# NVME.net
KiCad netlist of a schematic drawn in Altium Designer
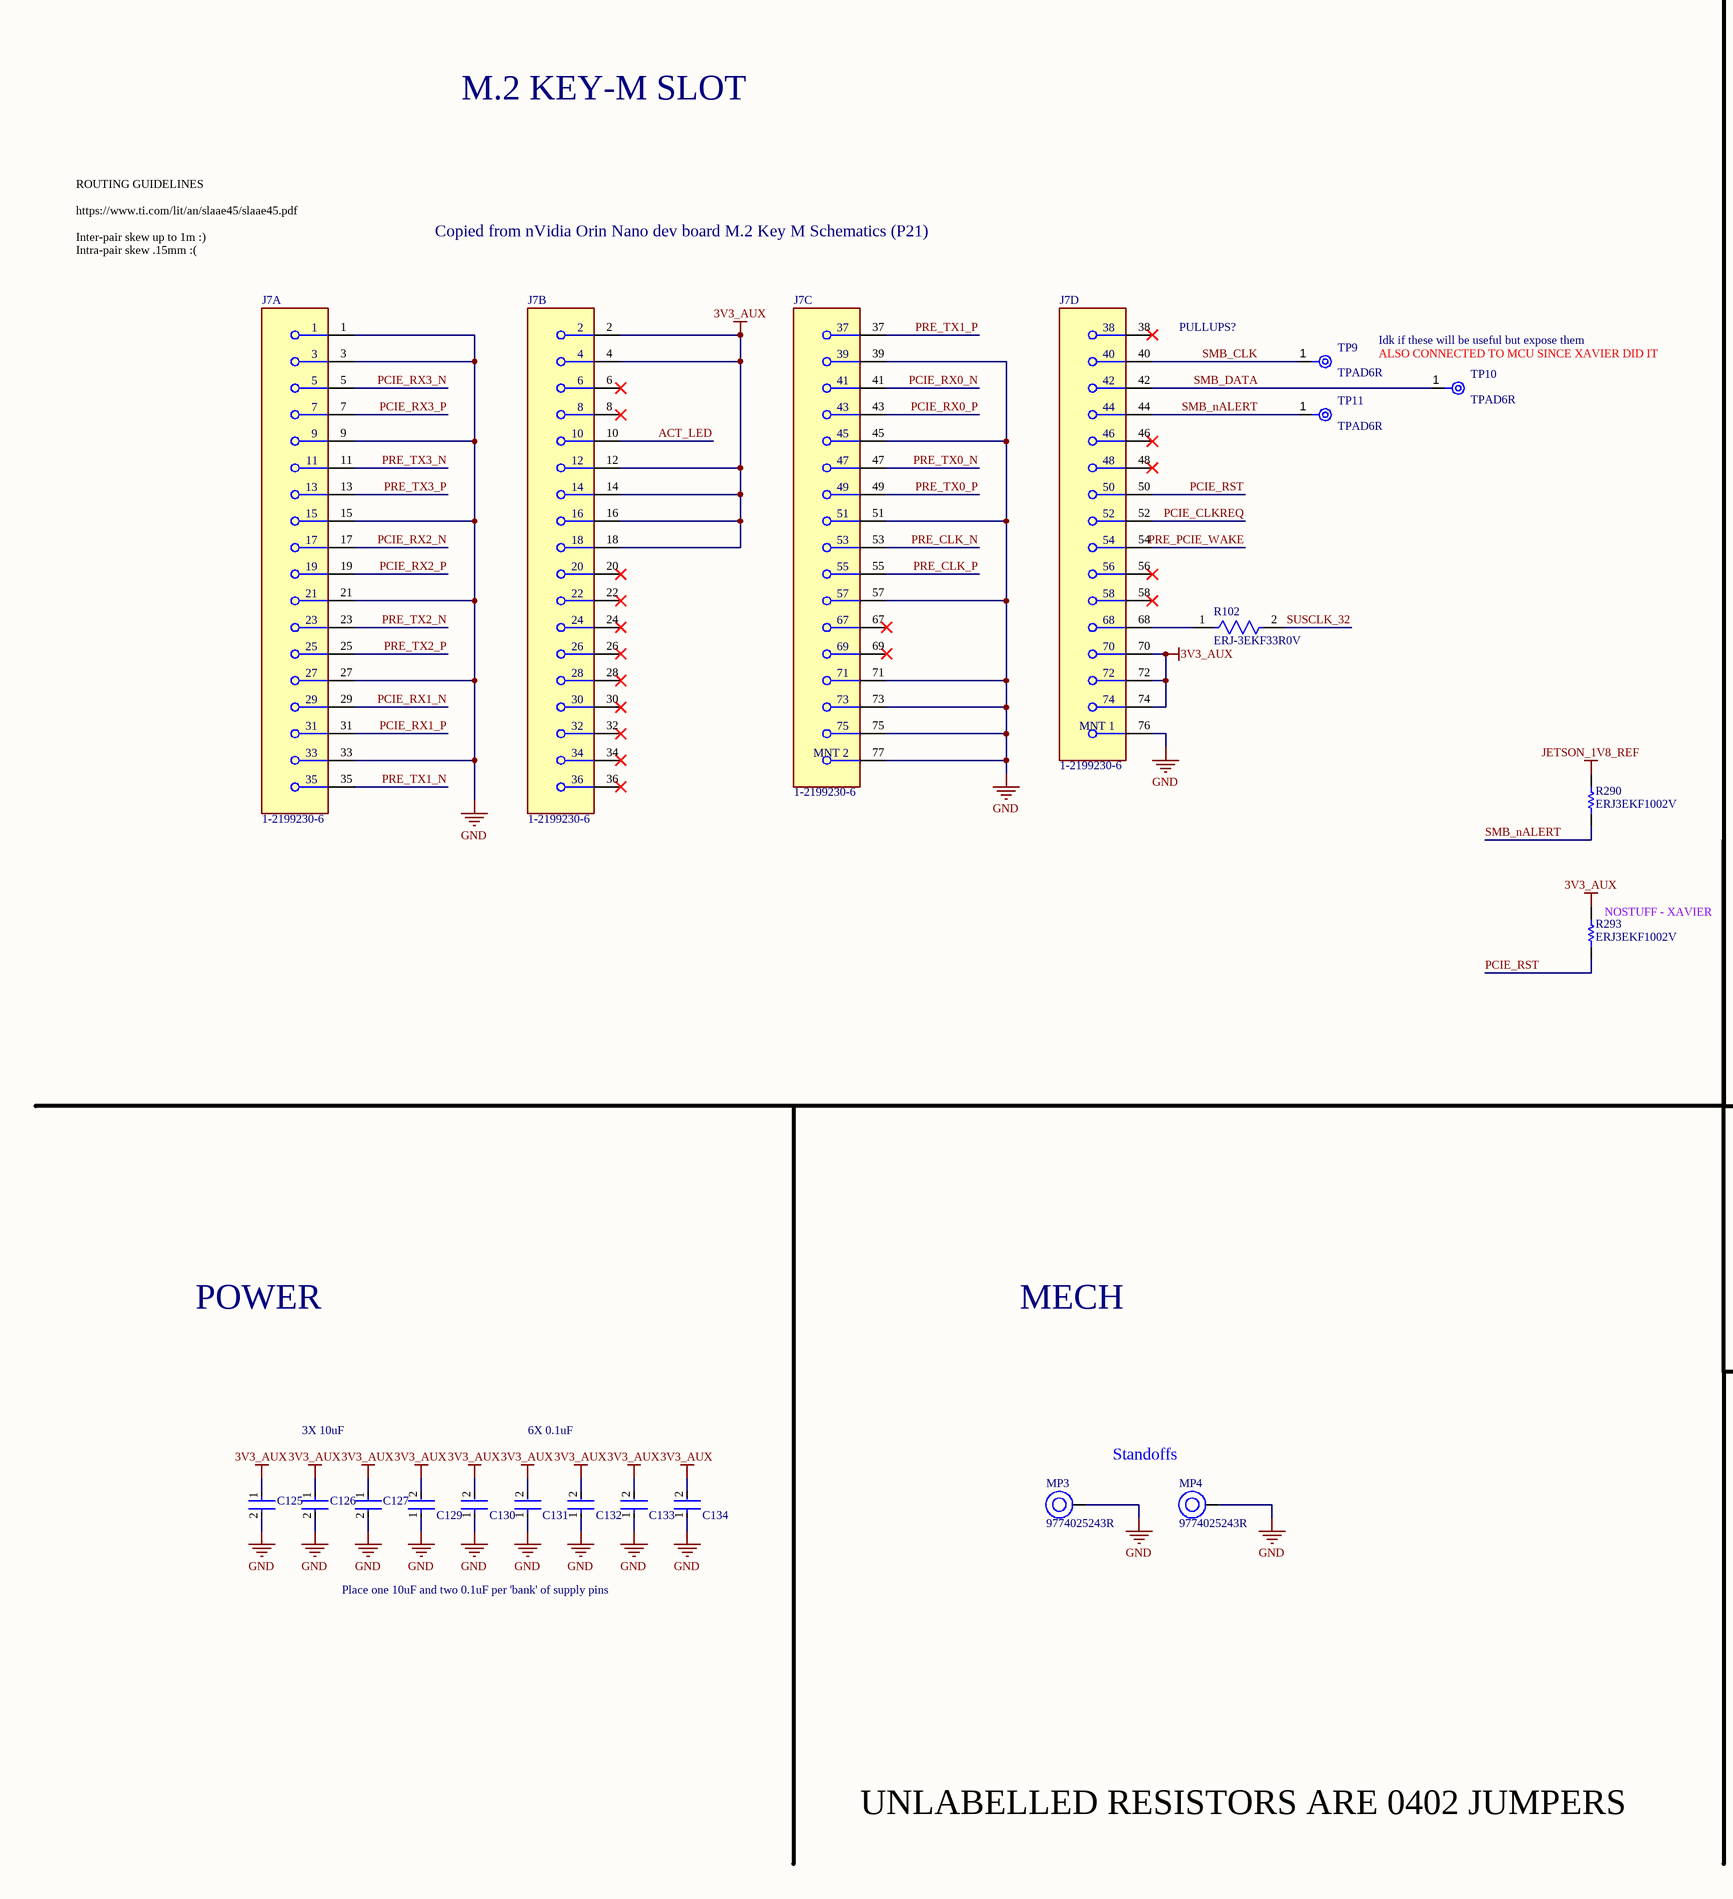
[diagram p0: NVME.SchDoc, left]
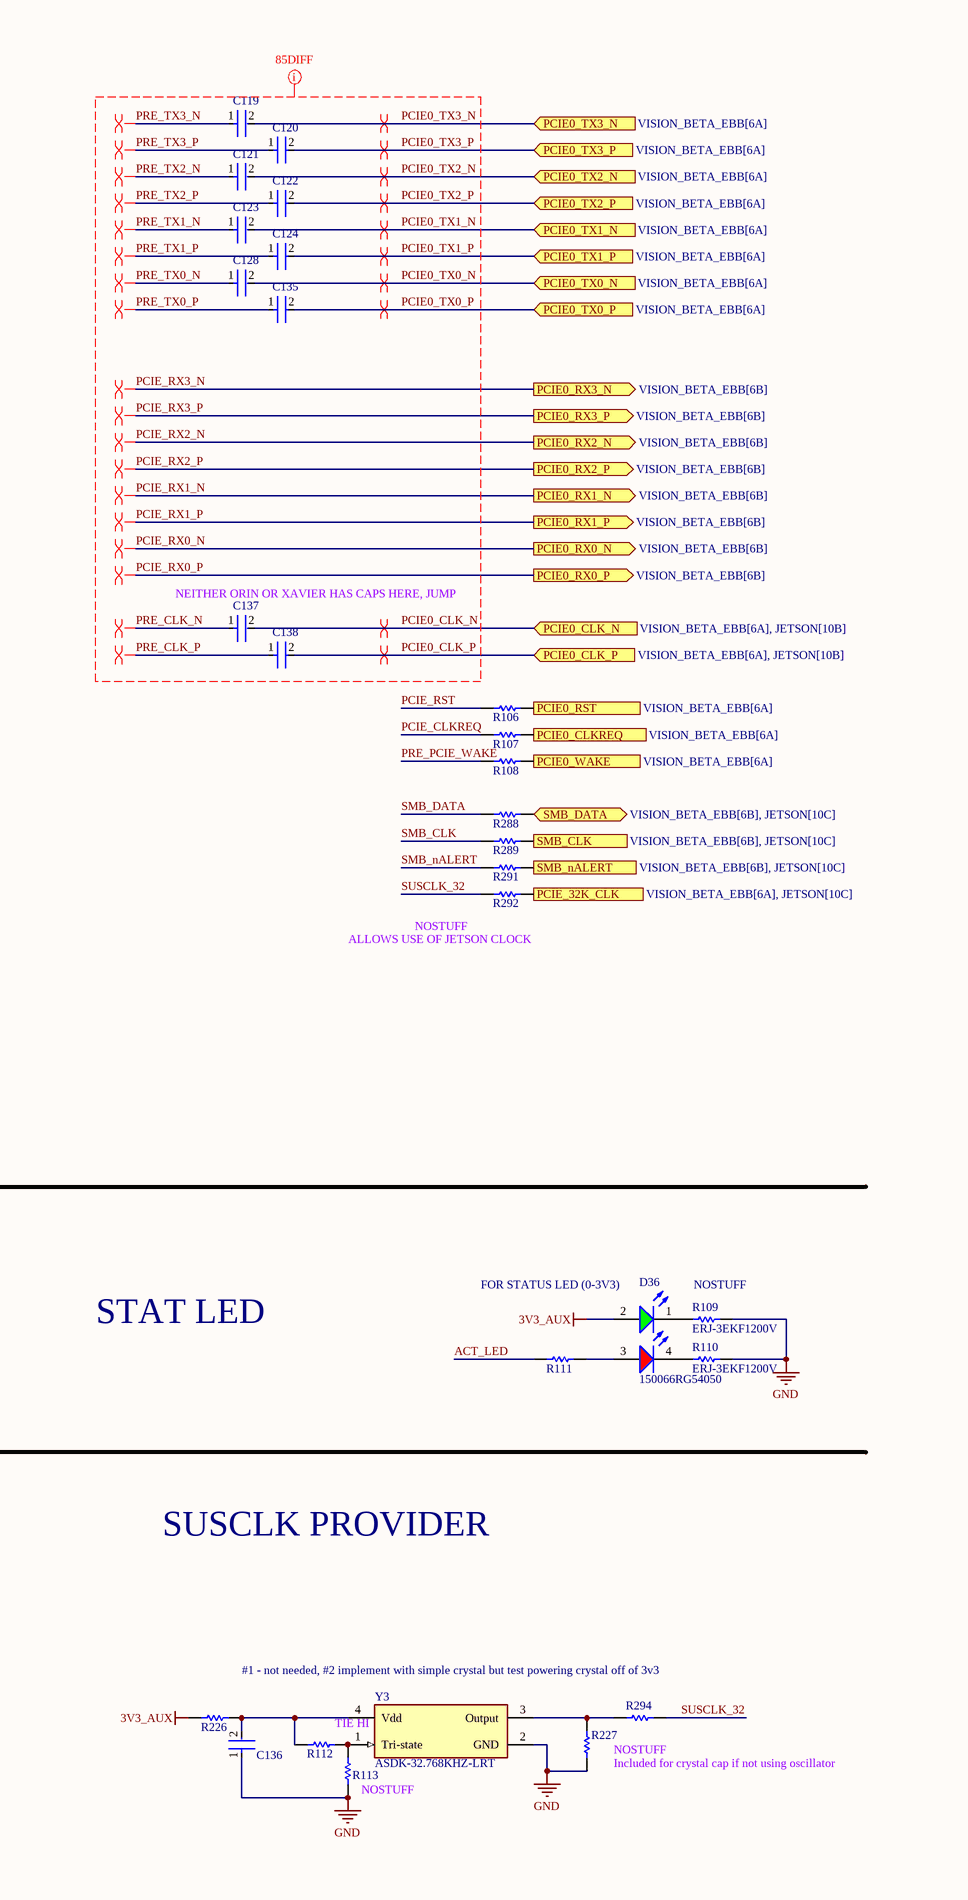
[diagram p1: NVME.SchDoc, right]

(export (version "E")
  (design (tool "Eeschema 10.0.6"))
  (components
    (comp (ref "C119")
      (value "C1005X7R1A224K050BB")
      (footprint "FP-C1005-050-0_05-IPC_C")
      (description "Multilayer Ceramic Capacitors 220nF ±10% 10V X7R SMD 0402")
      (fields (field (name "TOLERANCE") "10%"))
      (libsource (lib "Altium Content Vault") (part "b4654b650e69147ec39a6b967a45e02"))
    )
    (comp (ref "C120")
      (value "C1005X7R1A224K050BB")
      (footprint "FP-C1005-050-0_05-IPC_C")
      (description "Multilayer Ceramic Capacitors 220nF ±10% 10V X7R SMD 0402")
      (fields (field (name "TOLERANCE") "10%"))
      (libsource (lib "Altium Content Vault") (part "b4654b650e69147ec39a6b967a45e02"))
    )
    (comp (ref "C121")
      (value "C1005X7R1A224K050BB")
      (footprint "FP-C1005-050-0_05-IPC_C")
      (description "Multilayer Ceramic Capacitors 220nF ±10% 10V X7R SMD 0402")
      (fields (field (name "TOLERANCE") "10%"))
      (libsource (lib "Altium Content Vault") (part "b4654b650e69147ec39a6b967a45e02"))
    )
    (comp (ref "C122")
      (value "C1005X7R1A224K050BB")
      (footprint "FP-C1005-050-0_05-IPC_C")
      (description "Multilayer Ceramic Capacitors 220nF ±10% 10V X7R SMD 0402")
      (fields (field (name "TOLERANCE") "10%"))
      (libsource (lib "Altium Content Vault") (part "b4654b650e69147ec39a6b967a45e02"))
    )
    (comp (ref "C123")
      (value "C1005X7R1A224K050BB")
      (footprint "FP-C1005-050-0_05-IPC_C")
      (description "Multilayer Ceramic Capacitors 220nF ±10% 10V X7R SMD 0402")
      (fields (field (name "TOLERANCE") "10%"))
      (libsource (lib "Altium Content Vault") (part "b4654b650e69147ec39a6b967a45e02"))
    )
    (comp (ref "C124")
      (value "C1005X7R1A224K050BB")
      (footprint "FP-C1005-050-0_05-IPC_C")
      (description "Multilayer Ceramic Capacitors 220nF ±10% 10V X7R SMD 0402")
      (fields (field (name "TOLERANCE") "10%"))
      (libsource (lib "Altium Content Vault") (part "b4654b650e69147ec39a6b967a45e02"))
    )
    (comp (ref "C125")
      (value "GRM188R60J106ME47D")
      (footprint "FP-GRM188-0_1-e0_2_0_55-IPC_A")
      (description "Chip Multilayer Ceramic Capacitors for General Purpose, 0603, 10uF, X5R, 15%, 20%, 6.3V")
      (fields (field (name "VOLTAGE") "6.3V") (field (name "TOLERANCE") "20%"))
      (libsource (lib "Altium Content Vault") (part "02cd4be3c70576c341d710602a673aa"))
    )
    (comp (ref "C126")
      (value "GRM188R60J106ME47D")
      (footprint "FP-GRM188-0_1-e0_2_0_55-IPC_A")
      (description "Chip Multilayer Ceramic Capacitors for General Purpose, 0603, 10uF, X5R, 15%, 20%, 6.3V")
      (fields (field (name "VOLTAGE") "6.3V") (field (name "TOLERANCE") "20%"))
      (libsource (lib "Altium Content Vault") (part "02cd4be3c70576c341d710602a673aa"))
    )
    (comp (ref "C127")
      (value "GRM188R60J106ME47D")
      (footprint "FP-GRM188-0_1-e0_2_0_55-IPC_A")
      (description "Chip Multilayer Ceramic Capacitors for General Purpose, 0603, 10uF, X5R, 15%, 20%, 6.3V")
      (fields (field (name "VOLTAGE") "6.3V") (field (name "TOLERANCE") "20%"))
      (libsource (lib "Altium Content Vault") (part "02cd4be3c70576c341d710602a673aa"))
    )
    (comp (ref "C128")
      (value "C1005X7R1A224K050BB")
      (footprint "FP-C1005-050-0_05-IPC_C")
      (description "Multilayer Ceramic Capacitors 220nF ±10% 10V X7R SMD 0402")
      (fields (field (name "TOLERANCE") "10%"))
      (libsource (lib "Altium Content Vault") (part "b4654b650e69147ec39a6b967a45e02"))
    )
    (comp (ref "C129")
      (value "C1005X7R1H104K050BB")
      (footprint "FP-C1005-050-0_05-IPC_C")
      (description "Multilayer Ceramic Capacitors 100nF ±10% 50V X7R SMD 0402")
      (fields (field (name "VOLTAGE") "50V") (field (name "TOLERANCE") "10%"))
      (libsource (lib "Altium Content Vault") (part "b4654b650e69147ec39a6b967a45e02"))
    )
    (comp (ref "C130")
      (value "C1005X7R1H104K050BB")
      (footprint "FP-C1005-050-0_05-IPC_C")
      (description "Multilayer Ceramic Capacitors 100nF ±10% 50V X7R SMD 0402")
      (fields (field (name "VOLTAGE") "50V") (field (name "TOLERANCE") "10%"))
      (libsource (lib "Altium Content Vault") (part "b4654b650e69147ec39a6b967a45e02"))
    )
    (comp (ref "C131")
      (value "C1005X7R1H104K050BB")
      (footprint "FP-C1005-050-0_05-IPC_C")
      (description "Multilayer Ceramic Capacitors 100nF ±10% 50V X7R SMD 0402")
      (fields (field (name "VOLTAGE") "50V") (field (name "TOLERANCE") "10%"))
      (libsource (lib "Altium Content Vault") (part "b4654b650e69147ec39a6b967a45e02"))
    )
    (comp (ref "C132")
      (value "C1005X7R1H104K050BB")
      (footprint "FP-C1005-050-0_05-IPC_C")
      (description "Multilayer Ceramic Capacitors 100nF ±10% 50V X7R SMD 0402")
      (fields (field (name "VOLTAGE") "50V") (field (name "TOLERANCE") "10%"))
      (libsource (lib "Altium Content Vault") (part "b4654b650e69147ec39a6b967a45e02"))
    )
    (comp (ref "C133")
      (value "C1005X7R1H104K050BB")
      (footprint "FP-C1005-050-0_05-IPC_C")
      (description "Multilayer Ceramic Capacitors 100nF ±10% 50V X7R SMD 0402")
      (fields (field (name "VOLTAGE") "50V") (field (name "TOLERANCE") "10%"))
      (libsource (lib "Altium Content Vault") (part "b4654b650e69147ec39a6b967a45e02"))
    )
    (comp (ref "C134")
      (value "C1005X7R1H104K050BB")
      (footprint "FP-C1005-050-0_05-IPC_C")
      (description "Multilayer Ceramic Capacitors 100nF ±10% 50V X7R SMD 0402")
      (fields (field (name "VOLTAGE") "50V") (field (name "TOLERANCE") "10%"))
      (libsource (lib "Altium Content Vault") (part "b4654b650e69147ec39a6b967a45e02"))
    )
    (comp (ref "C135")
      (value "C1005X7R1A224K050BB")
      (footprint "FP-C1005-050-0_05-IPC_C")
      (description "Multilayer Ceramic Capacitors 220nF ±10% 10V X7R SMD 0402")
      (fields (field (name "TOLERANCE") "10%"))
      (libsource (lib "Altium Content Vault") (part "b4654b650e69147ec39a6b967a45e02"))
    )
    (comp (ref "C136")
      (value "C1005X7R1H104K050BB")
      (footprint "FP-C1005-050-0_05-IPC_C")
      (description "Multilayer Ceramic Capacitors 100nF ±10% 50V X7R SMD 0402")
      (fields (field (name "VOLTAGE") "50V") (field (name "TOLERANCE") "10%"))
      (libsource (lib "Altium Content Vault") (part "b4654b650e69147ec39a6b967a45e02"))
    )
    (comp (ref "C137")
      (value "C1005X7R1A224K050BB")
      (footprint "FP-C1005-050-0_05-IPC_C")
      (description "Multilayer Ceramic Capacitors 220nF ±10% 10V X7R SMD 0402")
      (fields (field (name "TOLERANCE") "10%"))
      (libsource (lib "Altium Content Vault") (part "b4654b650e69147ec39a6b967a45e02"))
    )
    (comp (ref "C138")
      (value "C1005X7R1A224K050BB")
      (footprint "FP-C1005-050-0_05-IPC_C")
      (description "Multilayer Ceramic Capacitors 220nF ±10% 10V X7R SMD 0402")
      (fields (field (name "TOLERANCE") "10%"))
      (libsource (lib "Altium Content Vault") (part "b4654b650e69147ec39a6b967a45e02"))
    )
    (comp (ref "D36")
      (value "150066RG54050")
      (footprint "WL-SBCD_0606")
      (description "Led, Red/Grn, 180Mcd/230Mcd, 624Nm/525Nm Rohs Compliant: Yes")
      (fields (field (name "SOURCE") "rgled.SchLib"))
      (libsource (lib "Space Concordia") (part "CMP-004-00034-2"))
    )
    (comp (ref "J7")
      (value "1-2199230-6")
      (footprint "FP-1-2199230-6-MFG")
      (description "CONN EDGE DUAL FMALE 67POS 0.020")
      (fields
        (field (name "MANUFACTURER") "TE")
        (field (name "OCTOPART") "https://octopart.com/1-2199230-6-te+connectivity-34969376")
      )
      (libsource (lib "Altium Content Vault") (part "bdc5cd39fb5e3adfc3cf7d042564072"))
    )
    (comp (ref "MP3")
      (value "9774025243R")
      (footprint "9774025243")
      (description "9774025243R Spacer Material: Steel, Tin-Plated Mounting: SMT Series: WA-SMST Thread D: M2")
      (libsource (lib "Altium Content Vault") (part "Spacer"))
    )
    (comp (ref "MP4")
      (value "9774025243R")
      (footprint "9774025243")
      (description "9774025243R Spacer Material: Steel, Tin-Plated Mounting: SMT Series: WA-SMST Thread D: M2")
      (libsource (lib "Altium Content Vault") (part "Spacer"))
    )
    (comp (ref "R102")
      (value "ERJ-3EKF33R0V")
      (footprint "FP-ERJ3EK-MFG")
      (description "RES SMD 33 OHM 1% 1/10W 0603")
      (fields (field (name "TOLERANCE") "1%"))
      (libsource (lib "Altium Content Vault") (part "1029c3af85768c4190bb7ad29bc67b5"))
    )
    (comp (ref "R106")
      (value "0402 JUMPER")
      (footprint "RESC1005X40X25ML05T05")
      (description "READ THE NAME")
      (libsource (lib "Space Concordia") (part "CMP-009-00206-2"))
    )
    (comp (ref "R107")
      (value "0402 JUMPER")
      (footprint "RESC1005X40X25ML05T05")
      (description "READ THE NAME")
      (libsource (lib "Space Concordia") (part "CMP-009-00206-2"))
    )
    (comp (ref "R108")
      (value "0402 JUMPER")
      (footprint "RESC1005X40X25ML05T05")
      (description "READ THE NAME")
      (libsource (lib "Space Concordia") (part "CMP-009-00206-2"))
    )
    (comp (ref "R109")
      (value "ERJ-3EKF1200V")
      (footprint "RESC1609X55X30ML15T15")
      (description "Chip Resistor, 120 Ohm, +/- 1%, 0.1 W, -55 to 155 degC, 0603 (1608 Metric), RoHS, Tape and Reel")
      (fields (field (name "TOLERANCE") "1%") (field (name "MANUFACTURER") "Panasonic"))
      (libsource (lib "Altium Content Vault") (part "RES-2"))
    )
    (comp (ref "R110")
      (value "ERJ-3EKF1200V")
      (footprint "RESC1609X55X30ML15T15")
      (description "Chip Resistor, 120 Ohm, +/- 1%, 0.1 W, -55 to 155 degC, 0603 (1608 Metric), RoHS, Tape and Reel")
      (fields (field (name "TOLERANCE") "1%") (field (name "MANUFACTURER") "Panasonic"))
      (libsource (lib "Altium Content Vault") (part "RES-2"))
    )
    (comp (ref "R111")
      (value "0402 JUMPER")
      (footprint "RESC1005X40X25ML05T05")
      (description "READ THE NAME")
      (libsource (lib "Space Concordia") (part "CMP-009-00206-2"))
    )
    (comp (ref "R112")
      (value "0402 JUMPER")
      (footprint "RESC1005X40X25ML05T05")
      (description "READ THE NAME")
      (libsource (lib "Space Concordia") (part "CMP-009-00206-2"))
    )
    (comp (ref "R113")
      (value "0402 JUMPER")
      (footprint "RESC1005X40X25ML05T05")
      (description "READ THE NAME")
      (libsource (lib "Space Concordia") (part "CMP-009-00206-2"))
    )
    (comp (ref "R226")
      (value "0402 JUMPER")
      (footprint "RESC1005X40X25ML05T05")
      (description "READ THE NAME")
      (libsource (lib "Space Concordia") (part "CMP-009-00206-2"))
    )
    (comp (ref "R227")
      (value "0402 JUMPER")
      (footprint "RESC1005X40X25ML05T05")
      (description "READ THE NAME")
      (libsource (lib "Space Concordia") (part "CMP-009-00206-2"))
    )
    (comp (ref "R288")
      (value "0402 JUMPER")
      (footprint "RESC1005X40X25ML05T05")
      (description "READ THE NAME")
      (libsource (lib "Space Concordia") (part "CMP-009-00206-2"))
    )
    (comp (ref "R289")
      (value "0402 JUMPER")
      (footprint "RESC1005X40X25ML05T05")
      (description "READ THE NAME")
      (libsource (lib "Space Concordia") (part "CMP-009-00206-2"))
    )
    (comp (ref "R290")
      (value "ERJ3EKF1002V")
      (footprint "RESC1609X55X30LL15T15")
      (description "Chip Resistor, 10 KOhm, +/- 1%, 0.1 W, -55 to 155 degC, 0603 (1608 Metric), RoHS, Tape and Reel")
      (fields (field (name "TOLERANCE") "1%") (field (name "MANUFACTURER") "Panasonic"))
      (libsource (lib "Altium Content Vault") (part "RES-2"))
    )
    (comp (ref "R291")
      (value "0402 JUMPER")
      (footprint "RESC1005X40X25ML05T05")
      (description "READ THE NAME")
      (libsource (lib "Space Concordia") (part "CMP-009-00206-2"))
    )
    (comp (ref "R292")
      (value "0402 JUMPER")
      (footprint "RESC1005X40X25ML05T05")
      (description "READ THE NAME")
      (libsource (lib "Space Concordia") (part "CMP-009-00206-2"))
    )
    (comp (ref "R293")
      (value "ERJ3EKF1002V")
      (footprint "RESC1609X55X30LL15T15")
      (description "Chip Resistor, 10 KOhm, +/- 1%, 0.1 W, -55 to 155 degC, 0603 (1608 Metric), RoHS, Tape and Reel")
      (fields (field (name "TOLERANCE") "1%") (field (name "MANUFACTURER") "Panasonic"))
      (libsource (lib "Altium Content Vault") (part "RES-2"))
    )
    (comp (ref "R294")
      (value "0402 JUMPER")
      (footprint "RESC1005X40X25ML05T05")
      (description "READ THE NAME")
      (libsource (lib "Space Concordia") (part "CMP-009-00206-2"))
    )
    (comp (ref "TP9")
      (value "TPAD6R")
      (footprint "New footprint 1")
      (description "Test Point .6mm")
      (libsource (lib "Space Concordia") (part "TP"))
    )
    (comp (ref "TP10")
      (value "TPAD6R")
      (footprint "New footprint 1")
      (description "Test Point .6mm")
      (libsource (lib "Space Concordia") (part "TP"))
    )
    (comp (ref "TP11")
      (value "TPAD6R")
      (footprint "New footprint 1")
      (description "Test Point .6mm")
      (libsource (lib "Space Concordia") (part "TP"))
    )
    (comp (ref "Y3")
      (value "ASDK-32.768KHZ-LRT")
      (footprint "FP-ASDK-MFG")
      (description "XTAL OSC XO 32.7680KHZ CMOS SMD")
      (libsource (lib "Altium Content Vault") (part "a7425352bb6ebc83bfd0f12a23808e7"))
    )
  )
  (nets
    (net (code "1") (name "/ACT_LED") (class "Default")
      (node (ref "J7") (pin "10") (pinfunction "10_10") (pintype "passive"))
      (node (ref "R111") (pin "1") (pinfunction "1_1") (pintype "passive"))
    )
    (net (code "2") (name "/PCIE0_CLKREQ") (class "Default")
      (node (ref "R107") (pin "2") (pinfunction "2_2") (pintype "passive"))
    )
    (net (code "3") (name "/PCIE0_CLK_N") (class "Default")
      (node (ref "C137") (pin "2") (pinfunction "2_2") (pintype "passive"))
    )
    (net (code "4") (name "/PCIE0_CLK_P") (class "Default")
      (node (ref "C138") (pin "2") (pinfunction "2_2") (pintype "passive"))
    )
    (net (code "5") (name "/PCIE0_RST") (class "Default")
      (node (ref "R106") (pin "2") (pinfunction "2_2") (pintype "passive"))
    )
    (net (code "6") (name "/PCIE0_TX0_N") (class "Default")
      (node (ref "C128") (pin "2") (pinfunction "2_2") (pintype "passive"))
    )
    (net (code "7") (name "/PCIE0_TX0_P") (class "Default")
      (node (ref "C135") (pin "2") (pinfunction "2_2") (pintype "passive"))
    )
    (net (code "8") (name "/PCIE0_TX1_N") (class "Default")
      (node (ref "C123") (pin "2") (pinfunction "2_2") (pintype "passive"))
    )
    (net (code "9") (name "/PCIE0_TX1_P") (class "Default")
      (node (ref "C124") (pin "2") (pinfunction "2_2") (pintype "passive"))
    )
    (net (code "10") (name "/PCIE0_TX2_N") (class "Default")
      (node (ref "C121") (pin "2") (pinfunction "2_2") (pintype "passive"))
    )
    (net (code "11") (name "/PCIE0_TX2_P") (class "Default")
      (node (ref "C122") (pin "2") (pinfunction "2_2") (pintype "passive"))
    )
    (net (code "12") (name "/PCIE0_TX3_N") (class "Default")
      (node (ref "C119") (pin "2") (pinfunction "2_2") (pintype "passive"))
    )
    (net (code "13") (name "/PCIE0_TX3_P") (class "Default")
      (node (ref "C120") (pin "2") (pinfunction "2_2") (pintype "passive"))
    )
    (net (code "14") (name "/PCIE0_WAKE") (class "Default")
      (node (ref "R108") (pin "2") (pinfunction "2_2") (pintype "passive"))
    )
    (net (code "15") (name "/PCIE_32K_CLK") (class "Default")
      (node (ref "R292") (pin "2") (pinfunction "2_2") (pintype "passive"))
    )
    (net (code "16") (name "/PCIE_CLKREQ") (class "Default")
      (node (ref "J7") (pin "52") (pinfunction "52_52") (pintype "passive"))
      (node (ref "R107") (pin "1") (pinfunction "1_1") (pintype "passive"))
    )
    (net (code "17") (name "/PCIE_RST") (class "Default")
      (node (ref "J7") (pin "50") (pinfunction "50_50") (pintype "passive"))
      (node (ref "R106") (pin "1") (pinfunction "1_1") (pintype "passive"))
      (node (ref "R293") (pin "1") (pinfunction "1_1") (pintype "passive"))
    )
    (net (code "18") (name "/PCIE_RX0_N") (class "Default")
      (node (ref "J7") (pin "41") (pinfunction "41_41") (pintype "passive"))
    )
    (net (code "19") (name "/PCIE_RX0_P") (class "Default")
      (node (ref "J7") (pin "43") (pinfunction "43_43") (pintype "passive"))
    )
    (net (code "20") (name "/PCIE_RX1_N") (class "Default")
      (node (ref "J7") (pin "29") (pinfunction "29_29") (pintype "passive"))
    )
    (net (code "21") (name "/PCIE_RX1_P") (class "Default")
      (node (ref "J7") (pin "31") (pinfunction "31_31") (pintype "passive"))
    )
    (net (code "22") (name "/PCIE_RX2_N") (class "Default")
      (node (ref "J7") (pin "17") (pinfunction "17_17") (pintype "passive"))
    )
    (net (code "23") (name "/PCIE_RX2_P") (class "Default")
      (node (ref "J7") (pin "19") (pinfunction "19_19") (pintype "passive"))
    )
    (net (code "24") (name "/PCIE_RX3_N") (class "Default")
      (node (ref "J7") (pin "5") (pinfunction "5_5") (pintype "passive"))
    )
    (net (code "25") (name "/PCIE_RX3_P") (class "Default")
      (node (ref "J7") (pin "7") (pinfunction "7_7") (pintype "passive"))
    )
    (net (code "26") (name "/PRE_CLK_N") (class "Default")
      (node (ref "C137") (pin "1") (pinfunction "1_1") (pintype "passive"))
      (node (ref "J7") (pin "53") (pinfunction "53_53") (pintype "passive"))
    )
    (net (code "27") (name "/PRE_CLK_P") (class "Default")
      (node (ref "C138") (pin "1") (pinfunction "1_1") (pintype "passive"))
      (node (ref "J7") (pin "55") (pinfunction "55_55") (pintype "passive"))
    )
    (net (code "28") (name "/PRE_PCIE_WAKE") (class "Default")
      (node (ref "J7") (pin "54") (pinfunction "54_54") (pintype "passive"))
      (node (ref "R108") (pin "1") (pinfunction "1_1") (pintype "passive"))
    )
    (net (code "29") (name "/PRE_TX0_N") (class "Default")
      (node (ref "C128") (pin "1") (pinfunction "1_1") (pintype "passive"))
      (node (ref "J7") (pin "47") (pinfunction "47_47") (pintype "passive"))
    )
    (net (code "30") (name "/PRE_TX0_P") (class "Default")
      (node (ref "C135") (pin "1") (pinfunction "1_1") (pintype "passive"))
      (node (ref "J7") (pin "49") (pinfunction "49_49") (pintype "passive"))
    )
    (net (code "31") (name "/PRE_TX1_N") (class "Default")
      (node (ref "C123") (pin "1") (pinfunction "1_1") (pintype "passive"))
      (node (ref "J7") (pin "35") (pinfunction "35_35") (pintype "passive"))
    )
    (net (code "32") (name "/PRE_TX1_P") (class "Default")
      (node (ref "C124") (pin "1") (pinfunction "1_1") (pintype "passive"))
      (node (ref "J7") (pin "37") (pinfunction "37_37") (pintype "passive"))
    )
    (net (code "33") (name "/PRE_TX2_N") (class "Default")
      (node (ref "C121") (pin "1") (pinfunction "1_1") (pintype "passive"))
      (node (ref "J7") (pin "23") (pinfunction "23_23") (pintype "passive"))
    )
    (net (code "34") (name "/PRE_TX2_P") (class "Default")
      (node (ref "C122") (pin "1") (pinfunction "1_1") (pintype "passive"))
      (node (ref "J7") (pin "25") (pinfunction "25_25") (pintype "passive"))
    )
    (net (code "35") (name "/PRE_TX3_N") (class "Default")
      (node (ref "C119") (pin "1") (pinfunction "1_1") (pintype "passive"))
      (node (ref "J7") (pin "11") (pinfunction "11_11") (pintype "passive"))
    )
    (net (code "36") (name "/PRE_TX3_P") (class "Default")
      (node (ref "C120") (pin "1") (pinfunction "1_1") (pintype "passive"))
      (node (ref "J7") (pin "13") (pinfunction "13_13") (pintype "passive"))
    )
    (net (code "37") (name "/SMB_CLK") (class "Default")
      (node (ref "J7") (pin "40") (pinfunction "40_40") (pintype "passive"))
      (node (ref "R289") (pin "1") (pinfunction "1_1") (pintype "passive"))
      (node (ref "TP9") (pin "1") (pinfunction "TP_1") (pintype "passive"))
    )
    (net (code "38") (name "/SMB_DATA") (class "Default")
      (node (ref "J7") (pin "42") (pinfunction "42_42") (pintype "passive"))
      (node (ref "R288") (pin "1") (pinfunction "1_1") (pintype "passive"))
      (node (ref "TP10") (pin "1") (pinfunction "TP_1") (pintype "passive"))
    )
    (net (code "39") (name "/SMB_nALERT") (class "Default")
      (node (ref "J7") (pin "44") (pinfunction "44_44") (pintype "passive"))
      (node (ref "R290") (pin "1") (pinfunction "1_1") (pintype "passive"))
      (node (ref "R291") (pin "1") (pinfunction "1_1") (pintype "passive"))
      (node (ref "TP11") (pin "1") (pinfunction "TP_1") (pintype "passive"))
    )
    (net (code "40") (name "/SUSCLK_32") (class "Default")
      (node (ref "R102") (pin "2") (pinfunction "2_2") (pintype "passive"))
      (node (ref "R292") (pin "1") (pinfunction "1_1") (pintype "passive"))
      (node (ref "R294") (pin "1") (pinfunction "1_1") (pintype "passive"))
    )
    (net (code "41") (name "3V3_AUX") (class "Default")
      (node (ref "C125") (pin "1") (pinfunction "1_1") (pintype "passive"))
      (node (ref "C126") (pin "1") (pinfunction "1_1") (pintype "passive"))
      (node (ref "C127") (pin "1") (pinfunction "1_1") (pintype "passive"))
      (node (ref "C129") (pin "2") (pinfunction "2_2") (pintype "passive"))
      (node (ref "C130") (pin "2") (pinfunction "2_2") (pintype "passive"))
      (node (ref "C131") (pin "2") (pinfunction "2_2") (pintype "passive"))
      (node (ref "C132") (pin "2") (pinfunction "2_2") (pintype "passive"))
      (node (ref "C133") (pin "2") (pinfunction "2_2") (pintype "passive"))
      (node (ref "C134") (pin "2") (pinfunction "2_2") (pintype "passive"))
      (node (ref "D36") (pin "2") (pinfunction "A_2") (pintype "passive"))
      (node (ref "J7") (pin "12") (pinfunction "12_12") (pintype "passive"))
      (node (ref "J7") (pin "14") (pinfunction "14_14") (pintype "passive"))
      (node (ref "J7") (pin "16") (pinfunction "16_16") (pintype "passive"))
      (node (ref "J7") (pin "18") (pinfunction "18_18") (pintype "passive"))
      (node (ref "J7") (pin "2") (pinfunction "2_2") (pintype "passive"))
      (node (ref "J7") (pin "4") (pinfunction "4_4") (pintype "passive"))
      (node (ref "J7") (pin "70") (pinfunction "70_70") (pintype "passive"))
      (node (ref "J7") (pin "72") (pinfunction "72_72") (pintype "passive"))
      (node (ref "J7") (pin "74") (pinfunction "74_74") (pintype "passive"))
      (node (ref "R226") (pin "1") (pinfunction "1_1") (pintype "passive"))
      (node (ref "R293") (pin "2") (pinfunction "2_2") (pintype "passive"))
    )
    (net (code "42") (name "GND") (class "Default")
      (node (ref "C125") (pin "2") (pinfunction "2_2") (pintype "passive"))
      (node (ref "C126") (pin "2") (pinfunction "2_2") (pintype "passive"))
      (node (ref "C127") (pin "2") (pinfunction "2_2") (pintype "passive"))
      (node (ref "C129") (pin "1") (pinfunction "1_1") (pintype "passive"))
      (node (ref "C130") (pin "1") (pinfunction "1_1") (pintype "passive"))
      (node (ref "C131") (pin "1") (pinfunction "1_1") (pintype "passive"))
      (node (ref "C132") (pin "1") (pinfunction "1_1") (pintype "passive"))
      (node (ref "C133") (pin "1") (pinfunction "1_1") (pintype "passive"))
      (node (ref "C134") (pin "1") (pinfunction "1_1") (pintype "passive"))
      (node (ref "C136") (pin "1") (pinfunction "1_1") (pintype "passive"))
      (node (ref "J7") (pin "1") (pinfunction "1_1") (pintype "passive"))
      (node (ref "J7") (pin "15") (pinfunction "15_15") (pintype "passive"))
      (node (ref "J7") (pin "21") (pinfunction "21_21") (pintype "passive"))
      (node (ref "J7") (pin "27") (pinfunction "27_27") (pintype "passive"))
      (node (ref "J7") (pin "3") (pinfunction "3_3") (pintype "passive"))
      (node (ref "J7") (pin "33") (pinfunction "33_33") (pintype "passive"))
      (node (ref "J7") (pin "39") (pinfunction "39_39") (pintype "passive"))
      (node (ref "J7") (pin "45") (pinfunction "45_45") (pintype "passive"))
      (node (ref "J7") (pin "51") (pinfunction "51_51") (pintype "passive"))
      (node (ref "J7") (pin "57") (pinfunction "57_57") (pintype "passive"))
      (node (ref "J7") (pin "71") (pinfunction "71_71") (pintype "passive"))
      (node (ref "J7") (pin "73") (pinfunction "73_73") (pintype "passive"))
      (node (ref "J7") (pin "75") (pinfunction "75_75") (pintype "passive"))
      (node (ref "J7") (pin "76") (pinfunction "MNT_1_76") (pintype "passive"))
      (node (ref "J7") (pin "77") (pinfunction "MNT_2_77") (pintype "passive"))
      (node (ref "J7") (pin "9") (pinfunction "9_9") (pintype "passive"))
      (node (ref "MP3") (pin "1") (pinfunction "1_1") (pintype "passive"))
      (node (ref "MP4") (pin "1") (pinfunction "1_1") (pintype "passive"))
      (node (ref "R109") (pin "1") (pinfunction "1_1") (pintype "passive"))
      (node (ref "R110") (pin "1") (pinfunction "1_1") (pintype "passive"))
      (node (ref "R113") (pin "1") (pinfunction "1_1") (pintype "passive"))
      (node (ref "R227") (pin "1") (pinfunction "1_1") (pintype "passive"))
      (node (ref "Y3") (pin "2") (pinfunction "GND_2") (pintype "power_in"))
    )
    (net (code "43") (name "JETSON_1V8_REF") (class "Default")
      (node (ref "R290") (pin "2") (pinfunction "2_2") (pintype "passive"))
    )
    (net (code "44") (name "Net-(D36-A-Pad3)") (class "Default")
      (node (ref "D36") (pin "3") (pinfunction "A_3") (pintype "passive"))
      (node (ref "R111") (pin "2") (pinfunction "2_2") (pintype "passive"))
    )
    (net (code "45") (name "Net-(D36-K-Pad1)") (class "Default")
      (node (ref "D36") (pin "1") (pinfunction "K_1") (pintype "passive"))
      (node (ref "R109") (pin "2") (pinfunction "2_2") (pintype "passive"))
    )
    (net (code "46") (name "Net-(D36-K-Pad4)") (class "Default")
      (node (ref "D36") (pin "4") (pinfunction "K_4") (pintype "passive"))
      (node (ref "R110") (pin "2") (pinfunction "2_2") (pintype "passive"))
    )
    (net (code "47") (name "Net-(J7-Pad68)") (class "Default")
      (node (ref "J7") (pin "68") (pinfunction "68_68") (pintype "passive"))
      (node (ref "R102") (pin "1") (pinfunction "1_1") (pintype "passive"))
    )
    (net (code "48") (name "Net-(Y3-Output)") (class "Default")
      (node (ref "R227") (pin "2") (pinfunction "2_2") (pintype "passive"))
      (node (ref "R294") (pin "2") (pinfunction "2_2") (pintype "passive"))
      (node (ref "Y3") (pin "3") (pinfunction "Output_3") (pintype "tri_state"))
    )
    (net (code "49") (name "Net-(Y3-Tri-state)") (class "Default")
      (node (ref "R112") (pin "2") (pinfunction "2_2") (pintype "passive"))
      (node (ref "R113") (pin "2") (pinfunction "2_2") (pintype "passive"))
      (node (ref "Y3") (pin "1") (pinfunction "Tri-state_1") (pintype "input"))
    )
    (net (code "50") (name "Net-(Y3-Vdd)") (class "Default")
      (node (ref "C136") (pin "2") (pinfunction "2_2") (pintype "passive"))
      (node (ref "R112") (pin "1") (pinfunction "1_1") (pintype "passive"))
      (node (ref "R226") (pin "2") (pinfunction "2_2") (pintype "passive"))
      (node (ref "Y3") (pin "4") (pinfunction "Vdd_4") (pintype "power_in"))
    )
    (net (code "51") (name "unconnected-(J7-Pad6)") (class "Default")
      (node (ref "J7") (pin "6") (pinfunction "6_6") (pintype "passive+no_connect"))
    )
    (net (code "52") (name "unconnected-(J7-Pad8)") (class "Default")
      (node (ref "J7") (pin "8") (pinfunction "8_8") (pintype "passive+no_connect"))
    )
    (net (code "53") (name "unconnected-(J7-Pad20)") (class "Default")
      (node (ref "J7") (pin "20") (pinfunction "20_20") (pintype "passive+no_connect"))
    )
    (net (code "54") (name "unconnected-(J7-Pad22)") (class "Default")
      (node (ref "J7") (pin "22") (pinfunction "22_22") (pintype "passive+no_connect"))
    )
    (net (code "55") (name "unconnected-(J7-Pad24)") (class "Default")
      (node (ref "J7") (pin "24") (pinfunction "24_24") (pintype "passive+no_connect"))
    )
    (net (code "56") (name "unconnected-(J7-Pad26)") (class "Default")
      (node (ref "J7") (pin "26") (pinfunction "26_26") (pintype "passive+no_connect"))
    )
    (net (code "57") (name "unconnected-(J7-Pad28)") (class "Default")
      (node (ref "J7") (pin "28") (pinfunction "28_28") (pintype "passive+no_connect"))
    )
    (net (code "58") (name "unconnected-(J7-Pad30)") (class "Default")
      (node (ref "J7") (pin "30") (pinfunction "30_30") (pintype "passive+no_connect"))
    )
    (net (code "59") (name "unconnected-(J7-Pad32)") (class "Default")
      (node (ref "J7") (pin "32") (pinfunction "32_32") (pintype "passive+no_connect"))
    )
    (net (code "60") (name "unconnected-(J7-Pad34)") (class "Default")
      (node (ref "J7") (pin "34") (pinfunction "34_34") (pintype "passive+no_connect"))
    )
    (net (code "61") (name "unconnected-(J7-Pad36)") (class "Default")
      (node (ref "J7") (pin "36") (pinfunction "36_36") (pintype "passive+no_connect"))
    )
    (net (code "62") (name "unconnected-(J7-Pad38)") (class "Default")
      (node (ref "J7") (pin "38") (pinfunction "38_38") (pintype "passive+no_connect"))
    )
    (net (code "63") (name "unconnected-(J7-Pad46)") (class "Default")
      (node (ref "J7") (pin "46") (pinfunction "46_46") (pintype "passive+no_connect"))
    )
    (net (code "64") (name "unconnected-(J7-Pad48)") (class "Default")
      (node (ref "J7") (pin "48") (pinfunction "48_48") (pintype "passive+no_connect"))
    )
    (net (code "65") (name "unconnected-(J7-Pad56)") (class "Default")
      (node (ref "J7") (pin "56") (pinfunction "56_56") (pintype "passive+no_connect"))
    )
    (net (code "66") (name "unconnected-(J7-Pad58)") (class "Default")
      (node (ref "J7") (pin "58") (pinfunction "58_58") (pintype "passive+no_connect"))
    )
    (net (code "67") (name "unconnected-(J7-Pad67)") (class "Default")
      (node (ref "J7") (pin "67") (pinfunction "67_67") (pintype "passive+no_connect"))
    )
    (net (code "68") (name "unconnected-(J7-Pad69)") (class "Default")
      (node (ref "J7") (pin "69") (pinfunction "69_69") (pintype "passive+no_connect"))
    )
    (net (code "69") (name "unconnected-(R288-Pad2)") (class "Default")
      (node (ref "R288") (pin "2") (pinfunction "2_2") (pintype "passive"))
    )
    (net (code "70") (name "unconnected-(R289-Pad2)") (class "Default")
      (node (ref "R289") (pin "2") (pinfunction "2_2") (pintype "passive"))
    )
    (net (code "71") (name "unconnected-(R291-Pad2)") (class "Default")
      (node (ref "R291") (pin "2") (pinfunction "2_2") (pintype "passive"))
    )
  )
)
